# MCU.net
KiCad netlist of a schematic drawn in Altium Designer
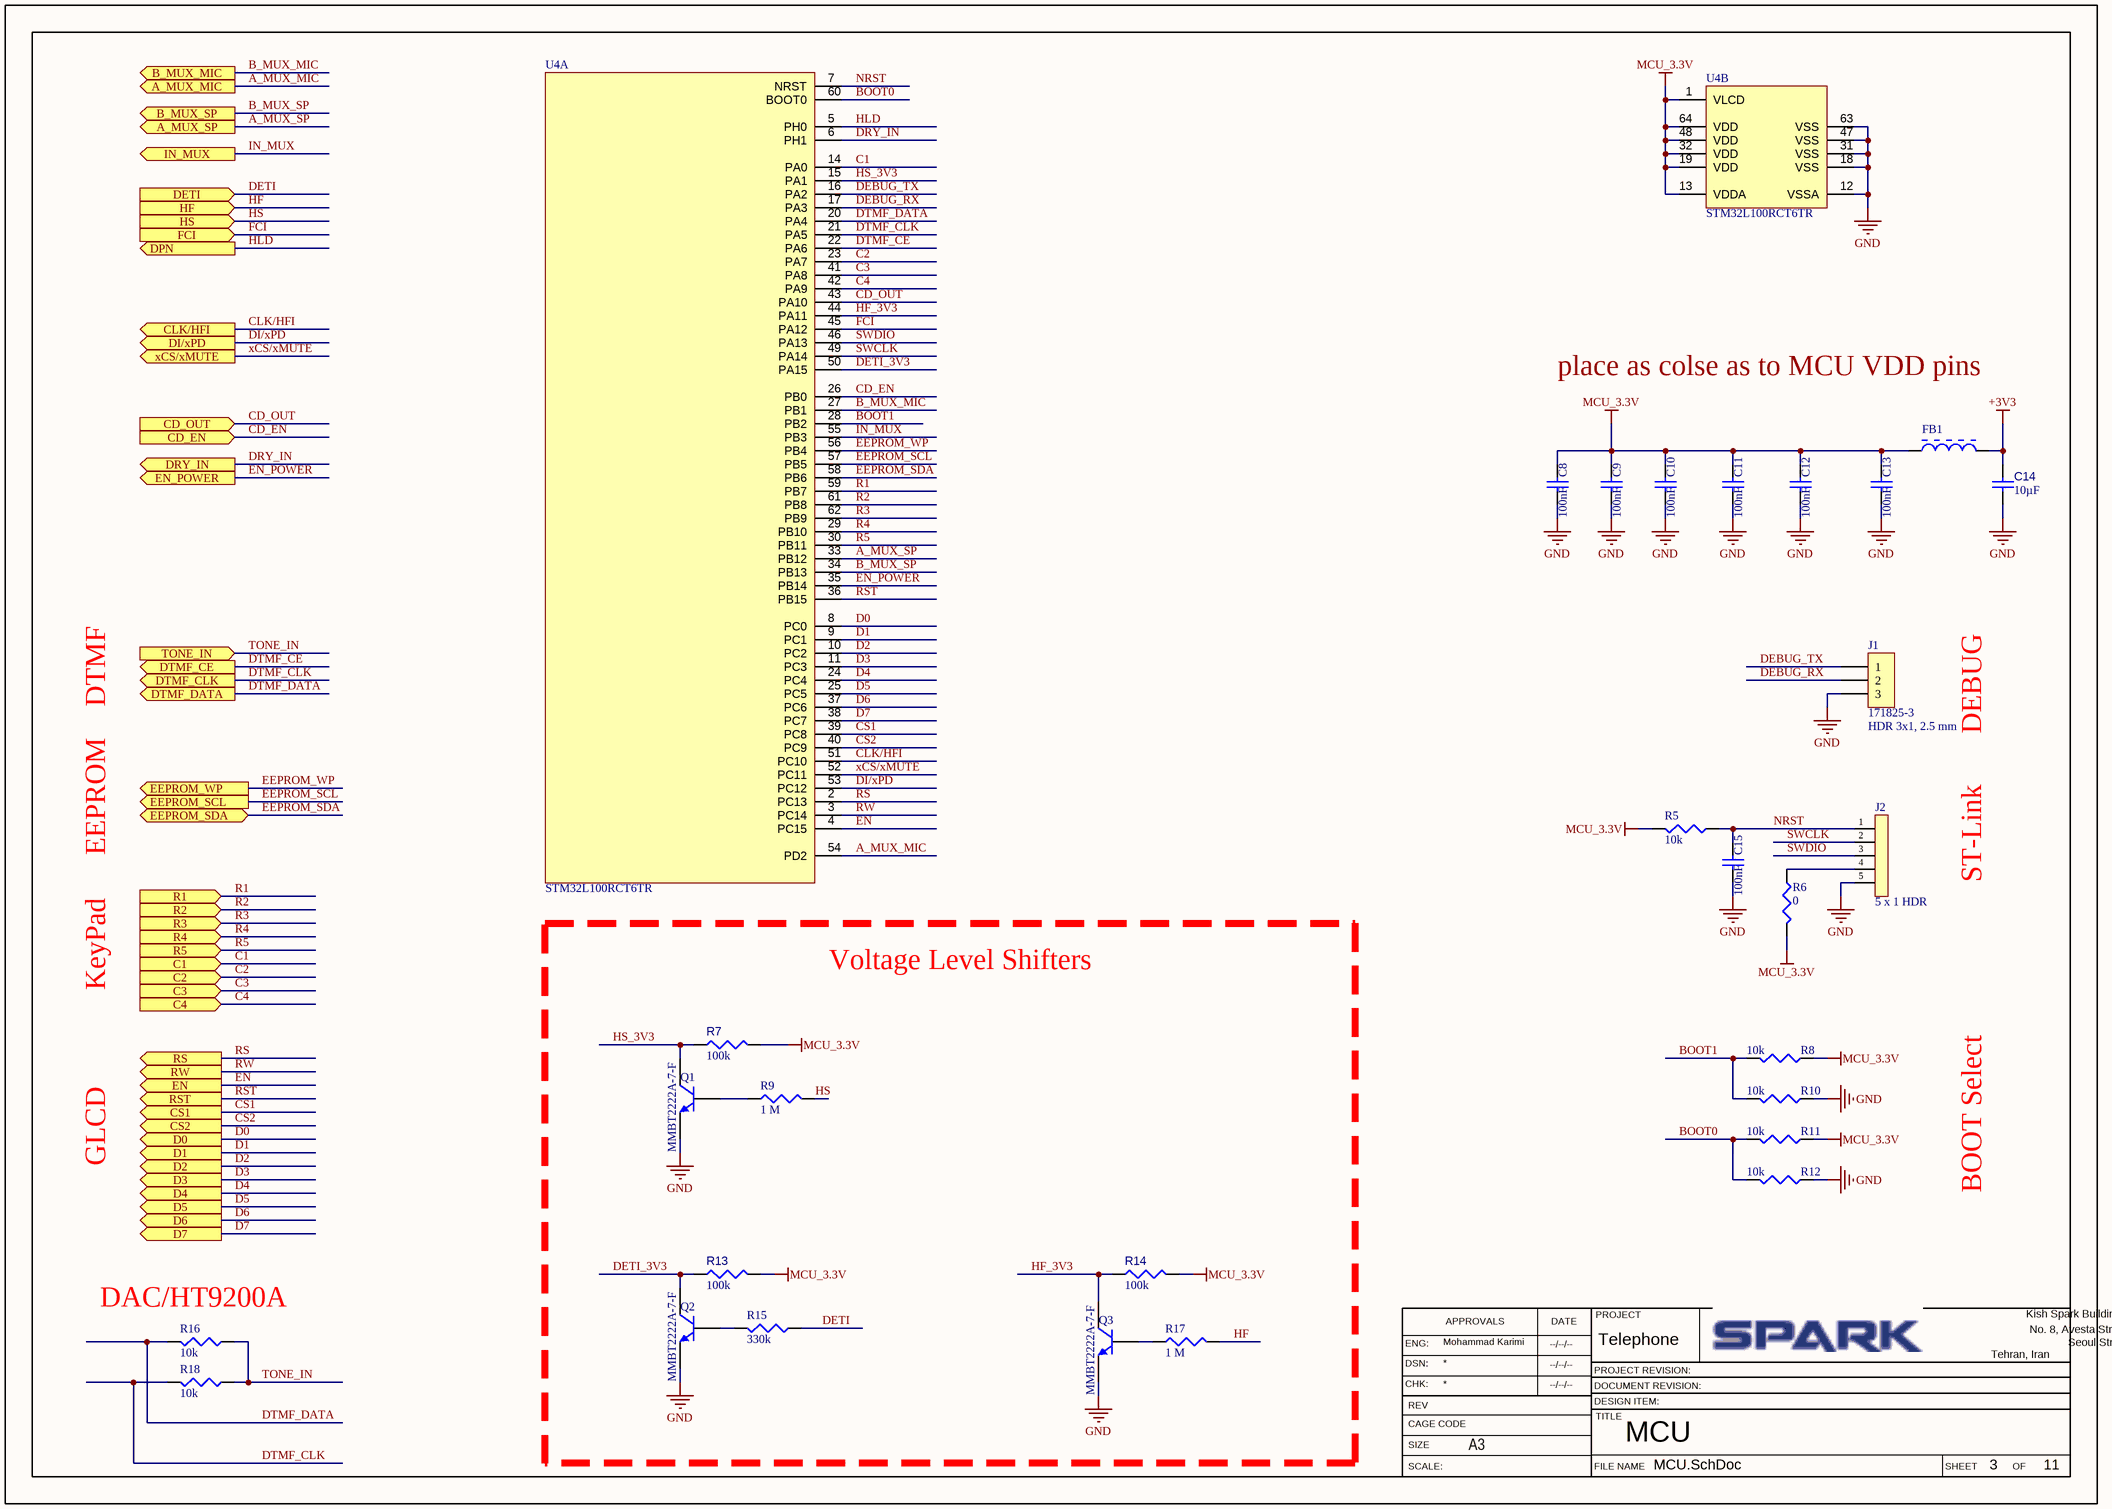
[diagram p0: MCU.SchDoc]

(export (version "E")
  (design (tool "Eeschema 10.0.6"))
  (components
    (comp (ref "C8")
      (value "100nF")
      (footprint "C0603")
      (description "YAGEO - CC0603KRX7R8BB104 - CERAMIC CAPACITOR, 0.1UF, 25V, X7R, 10%, 0603, FULL REEL")
      (fields
        (field (name "TOLERANCE") "10%")
        (field (name "VOLTAGE") "25V")
        (field (name "SOURCE") "PTZLib.SchLib")
      )
      (libsource (lib "Kish Spark") (part "CAP-NP-2"))
    )
    (comp (ref "C9")
      (value "100nF")
      (footprint "C0603")
      (description "YAGEO - CC0603KRX7R8BB104 - CERAMIC CAPACITOR, 0.1UF, 25V, X7R, 10%, 0603, FULL REEL")
      (fields
        (field (name "TOLERANCE") "10%")
        (field (name "VOLTAGE") "25V")
        (field (name "SOURCE") "PTZLib.SchLib")
      )
      (libsource (lib "Kish Spark") (part "CAP-NP-2"))
    )
    (comp (ref "C10")
      (value "100nF")
      (footprint "C0603")
      (description "YAGEO - CC0603KRX7R8BB104 - CERAMIC CAPACITOR, 0.1UF, 25V, X7R, 10%, 0603, FULL REEL")
      (fields
        (field (name "TOLERANCE") "10%")
        (field (name "VOLTAGE") "25V")
        (field (name "SOURCE") "PTZLib.SchLib")
      )
      (libsource (lib "Kish Spark") (part "CAP-NP-2"))
    )
    (comp (ref "C11")
      (value "100nF")
      (footprint "C0603")
      (description "YAGEO - CC0603KRX7R8BB104 - CERAMIC CAPACITOR, 0.1UF, 25V, X7R, 10%, 0603, FULL REEL")
      (fields
        (field (name "TOLERANCE") "10%")
        (field (name "VOLTAGE") "25V")
        (field (name "SOURCE") "PTZLib.SchLib")
      )
      (libsource (lib "Kish Spark") (part "CAP-NP-2"))
    )
    (comp (ref "C12")
      (value "100nF")
      (footprint "C0603")
      (description "YAGEO - CC0603KRX7R8BB104 - CERAMIC CAPACITOR, 0.1UF, 25V, X7R, 10%, 0603, FULL REEL")
      (fields
        (field (name "TOLERANCE") "10%")
        (field (name "VOLTAGE") "25V")
        (field (name "SOURCE") "PTZLib.SchLib")
      )
      (libsource (lib "Kish Spark") (part "CAP-NP-2"))
    )
    (comp (ref "C13")
      (value "100nF")
      (footprint "C0603")
      (description "YAGEO - CC0603KRX7R8BB104 - CERAMIC CAPACITOR, 0.1UF, 25V, X7R, 10%, 0603, FULL REEL")
      (fields
        (field (name "TOLERANCE") "10%")
        (field (name "VOLTAGE") "25V")
        (field (name "SOURCE") "PTZLib.SchLib")
      )
      (libsource (lib "Kish Spark") (part "CAP-NP-2"))
    )
    (comp (ref "C14")
      (value "10µF")
      (footprint "0805")
      (description "Ceramic Capacitor, 10UF, 6.3V, X5R, 10%, 0805, Full Reel")
      (fields
        (field (name "MANUFACTURER") "KEMET")
        (field (name "MANUFACTURER PART NUMBER") "C0805C106K9PACTU")
      )
      (libsource (lib "Kish Spark") (part "CAP-NP-2"))
    )
    (comp (ref "C15")
      (value "100nF")
      (footprint "C0603")
      (description "YAGEO - CC0603KRX7R8BB104 - CERAMIC CAPACITOR, 0.1UF, 25V, X7R, 10%, 0603, FULL REEL")
      (fields
        (field (name "TOLERANCE") "10%")
        (field (name "VOLTAGE") "25V")
        (field (name "SOURCE") "PTZLib.SchLib")
      )
      (libsource (lib "Kish Spark") (part "CAP-NP-2"))
    )
    (comp (ref "FB1")
      (value "CMP-006-00051-1")
      (footprint "R0603")
      (description "Ferrite Beads 0603 60ohm")
      (fields (field (name "TOLERANCE") "25%") (field (name "SOURCE") "PTZLib.SchLib"))
      (libsource (lib "Kish Spark") (part "FerriteBead"))
    )
    (comp (ref "J1")
      (value "171825-3")
      (footprint "HDR_MALE_1x3_2.5MM_AMP EI_VERT")
      (description "EI Series 3 Position 2.5 mm Single Row Through Hole Shrouded Header")
      (fields (field (name "ALTIUM_VALUE") "HDR 3x1, 2.5 mm") (field (name "MANUFACTURER") "TE Connectivity"))
      (libsource (lib "Kish Spark") (part "171825-3"))
    )
    (comp (ref "J2")
      (value "5 x 1 HDR")
      (footprint "HDR_male_1x5_2.54mm")
      (description "Manufacturer Part # :   9-146278-0")
      (fields (field (name "SOURCE") "PTZLib.SchLib"))
      (libsource (lib "Kish Spark") (part "5 x 1 HDR"))
    )
    (comp (ref "Q1")
      (value "MMBT2222A-7-F")
      (footprint "SOT23127P600-8N")
      (description "MMBT2222 Series NPN 350 mW 40 V 600 mA SMT Small Signal Transistor - SOT-23")
      (fields
        (field (name "MANUFACTURER") "Diodes")
        (field (name "VOLTAGE") "40V")
        (field (name "SOURCE") "PTZ.SCHLIB")
      )
      (libsource (lib "Kish Spark") (part "BJT-NPN-EBC-3"))
    )
    (comp (ref "Q2")
      (value "MMBT2222A-7-F")
      (footprint "SOT23127P600-8N")
      (description "MMBT2222 Series NPN 350 mW 40 V 600 mA SMT Small Signal Transistor - SOT-23")
      (fields
        (field (name "MANUFACTURER") "Diodes")
        (field (name "VOLTAGE") "40V")
        (field (name "SOURCE") "PTZ.SCHLIB")
      )
      (libsource (lib "Kish Spark") (part "BJT-NPN-EBC-3"))
    )
    (comp (ref "Q3")
      (value "MMBT2222A-7-F")
      (footprint "SOT23127P600-8N")
      (description "MMBT2222 Series NPN 350 mW 40 V 600 mA SMT Small Signal Transistor - SOT-23")
      (fields
        (field (name "MANUFACTURER") "Diodes")
        (field (name "VOLTAGE") "40V")
        (field (name "SOURCE") "PTZ.SCHLIB")
      )
      (libsource (lib "Kish Spark") (part "BJT-NPN-EBC-3"))
    )
    (comp (ref "R5")
      (value "10k")
      (footprint "R0603")
      (description "Res Thick Film 0603 10K Ohm 5% 1/10W 200ppm/C Molded SMD SMD Paper T/R")
      (fields
        (field (name "TOLERANCE") "5%")
        (field (name "Comment") "CRCW060310K0JNEA")
        (field (name "SOURCE") "PTZLib.SchLib")
      )
      (libsource (lib "Kish Spark") (part "RN73R1JTTD3302F10"))
    )
    (comp (ref "R6")
      (value "0")
      (footprint "0805")
      (description "RC Series 0805 0.125 W 0 Ohm Jumper SMT Thick Film Chip Resistor")
      (fields
        (field (name "MANUFACTURER") "Yageo")
        (field (name "MANUFACTURER PART NUMBER") "RC0805FR-070RL")
      )
      (libsource (lib "Kish Spark") (part "RC0805FR-1018KL (2)"))
    )
    (comp (ref "R7")
      (value "100k")
      (footprint "R0805")
      (description "Res Thick Film 0805 100K Ohm 1% 1/8W ±100ppm/°C Molded SMD Paper T/R")
      (fields (field (name "POWER") "125mW") (field (name "TOLERANCE") "1%"))
      (libsource (lib "Kish Spark") (part "RES-2"))
    )
    (comp (ref "R8")
      (value "10k")
      (footprint "R0603")
      (description "Res Thick Film 0603 10K Ohm 5% 1/10W 200ppm/C Molded SMD SMD Paper T/R")
      (fields
        (field (name "TOLERANCE") "5%")
        (field (name "Comment") "CRCW060310K0JNEA")
        (field (name "SOURCE") "PTZLib.SchLib")
      )
      (libsource (lib "Kish Spark") (part "RN73R1JTTD3302F10"))
    )
    (comp (ref "R9")
      (value "1 M")
      (footprint "0805")
      (description "Res Thick Film 0805 1M Ohm 5% 0.125W(1/8W) ±200ppm/°C Pad SMD T/R")
      (fields
        (field (name "MANUFACTURER") "Vishay")
        (field (name "MANUFACTURER PART NUMBER") "CRCW08051M00JNEAC")
      )
      (libsource (lib "Kish Spark") (part "RC0805FR-1018KL (2)"))
    )
    (comp (ref "R10")
      (value "10k")
      (footprint "R0603")
      (description "Res Thick Film 0603 10K Ohm 5% 1/10W 200ppm/C Molded SMD SMD Paper T/R")
      (fields
        (field (name "TOLERANCE") "5%")
        (field (name "Comment") "CRCW060310K0JNEA")
        (field (name "SOURCE") "PTZLib.SchLib")
      )
      (libsource (lib "Kish Spark") (part "RN73R1JTTD3302F10"))
    )
    (comp (ref "R11")
      (value "10k")
      (footprint "R0603")
      (description "Res Thick Film 0603 10K Ohm 5% 1/10W 200ppm/C Molded SMD SMD Paper T/R")
      (fields
        (field (name "TOLERANCE") "5%")
        (field (name "Comment") "CRCW060310K0JNEA")
        (field (name "SOURCE") "PTZLib.SchLib")
      )
      (libsource (lib "Kish Spark") (part "RN73R1JTTD3302F10"))
    )
    (comp (ref "R12")
      (value "10k")
      (footprint "R0603")
      (description "Res Thick Film 0603 10K Ohm 5% 1/10W 200ppm/C Molded SMD SMD Paper T/R")
      (fields
        (field (name "TOLERANCE") "5%")
        (field (name "Comment") "CRCW060310K0JNEA")
        (field (name "SOURCE") "PTZLib.SchLib")
      )
      (libsource (lib "Kish Spark") (part "RN73R1JTTD3302F10"))
    )
    (comp (ref "R13")
      (value "100k")
      (footprint "R0805")
      (description "Res Thick Film 0805 100K Ohm 1% 1/8W ±100ppm/°C Molded SMD Paper T/R")
      (fields (field (name "POWER") "125mW") (field (name "TOLERANCE") "1%"))
      (libsource (lib "Kish Spark") (part "RES-2"))
    )
    (comp (ref "R14")
      (value "100k")
      (footprint "R0805")
      (description "Res Thick Film 0805 100K Ohm 1% 1/8W ±100ppm/°C Molded SMD Paper T/R")
      (fields (field (name "POWER") "125mW") (field (name "TOLERANCE") "1%"))
      (libsource (lib "Kish Spark") (part "RES-2"))
    )
    (comp (ref "R15")
      (value "330k")
      (footprint "0805")
      (description "Res Thick Film 0805 330K Ohm 1% 1/8W ±100ppm/°C Molded SMD Paper T/R")
      (fields
        (field (name "MANUFACTURER") "Yageo")
        (field (name "MANUFACTURER PART NUMBER") "RC0805FR-07330KL")
      )
      (libsource (lib "Kish Spark") (part "RC0805FR-1018KL (2)"))
    )
    (comp (ref "R16")
      (value "10k")
      (footprint "R0603")
      (description "Res Thick Film 0603 10K Ohm 5% 1/10W 200ppm/C Molded SMD SMD Paper T/R")
      (fields
        (field (name "TOLERANCE") "5%")
        (field (name "Comment") "CRCW060310K0JNEA")
        (field (name "SOURCE") "PTZLib.SchLib")
      )
      (libsource (lib "Kish Spark") (part "RN73R1JTTD3302F10"))
    )
    (comp (ref "R17")
      (value "1 M")
      (footprint "0805")
      (description "Res Thick Film 0805 1M Ohm 5% 0.125W(1/8W) ±200ppm/°C Pad SMD T/R")
      (fields
        (field (name "MANUFACTURER") "Vishay")
        (field (name "MANUFACTURER PART NUMBER") "CRCW08051M00JNEAC")
      )
      (libsource (lib "Kish Spark") (part "RC0805FR-1018KL (2)"))
    )
    (comp (ref "R18")
      (value "10k")
      (footprint "R0603")
      (description "Res Thick Film 0603 10K Ohm 5% 1/10W 200ppm/C Molded SMD SMD Paper T/R")
      (fields
        (field (name "TOLERANCE") "5%")
        (field (name "Comment") "CRCW060310K0JNEA")
        (field (name "SOURCE") "PTZLib.SchLib")
      )
      (libsource (lib "Kish Spark") (part "RN73R1JTTD3302F10"))
    )
    (comp (ref "U4")
      (value "STM32L100RCT6TR")
      (footprint "STM32L100RCT6TR-Footprint-1")
      (description "Ultra-low-power 32-bit Value Line ARM Cortex-M3 MCU with 256 Kbytes Flash, 32 MHz CPU, LCD, USB")
      (fields (field (name "MANUFACTURER") "STMicroelectronics"))
      (libsource (lib "Kish Spark") (part "STM32L100RCT6TR"))
    )
  )
  (nets
    (net (code "1") (name "+3V3") (class "Default")
      (node (ref "C14") (pin "1") (pinfunction "1_1") (pintype "passive"))
      (node (ref "FB1") (pin "2") (pinfunction "2_2") (pintype "passive"))
    )
    (net (code "2") (name "/A_MUX_MIC") (class "Default")
      (node (ref "U4") (pin "54") (pinfunction "PD2_54") (pintype "passive"))
    )
    (net (code "3") (name "/A_MUX_SP") (class "Default")
      (node (ref "U4") (pin "33") (pinfunction "PB12_33") (pintype "passive"))
    )
    (net (code "4") (name "/BOOT0") (class "Default")
      (node (ref "R11") (pin "2") (pinfunction "2_2") (pintype "passive"))
      (node (ref "R12") (pin "2") (pinfunction "2_2") (pintype "passive"))
      (node (ref "U4") (pin "60") (pinfunction "BOOT0_60") (pintype "passive"))
    )
    (net (code "5") (name "/BOOT1") (class "Default")
      (node (ref "R10") (pin "2") (pinfunction "2_2") (pintype "passive"))
      (node (ref "R8") (pin "2") (pinfunction "2_2") (pintype "passive"))
      (node (ref "U4") (pin "28") (pinfunction "PB2_28") (pintype "passive"))
    )
    (net (code "6") (name "/B_MUX_MIC") (class "Default")
      (node (ref "U4") (pin "27") (pinfunction "PB1_27") (pintype "passive"))
    )
    (net (code "7") (name "/B_MUX_SP") (class "Default")
      (node (ref "U4") (pin "34") (pinfunction "PB13_34") (pintype "passive"))
    )
    (net (code "8") (name "/C1") (class "Default")
      (node (ref "U4") (pin "14") (pinfunction "PA0_14") (pintype "passive"))
    )
    (net (code "9") (name "/C2") (class "Default")
      (node (ref "U4") (pin "23") (pinfunction "PA7_23") (pintype "passive"))
    )
    (net (code "10") (name "/C3") (class "Default")
      (node (ref "U4") (pin "41") (pinfunction "PA8_41") (pintype "passive"))
    )
    (net (code "11") (name "/C4") (class "Default")
      (node (ref "U4") (pin "42") (pinfunction "PA9_42") (pintype "passive"))
    )
    (net (code "12") (name "/CD_EN") (class "Default")
      (node (ref "U4") (pin "26") (pinfunction "PB0_26") (pintype "passive"))
    )
    (net (code "13") (name "/CD_OUT") (class "Default")
      (node (ref "U4") (pin "43") (pinfunction "PA10_43") (pintype "passive"))
    )
    (net (code "14") (name "/CLK{slash}HFI") (class "Default")
      (node (ref "U4") (pin "51") (pinfunction "PC10_51") (pintype "passive"))
    )
    (net (code "15") (name "/CS1") (class "Default")
      (node (ref "U4") (pin "39") (pinfunction "PC8_39") (pintype "passive"))
    )
    (net (code "16") (name "/CS2") (class "Default")
      (node (ref "U4") (pin "40") (pinfunction "PC9_40") (pintype "passive"))
    )
    (net (code "17") (name "/D0") (class "Default")
      (node (ref "U4") (pin "8") (pinfunction "PC0_8") (pintype "passive"))
    )
    (net (code "18") (name "/D1") (class "Default")
      (node (ref "U4") (pin "9") (pinfunction "PC1_9") (pintype "passive"))
    )
    (net (code "19") (name "/D2") (class "Default")
      (node (ref "U4") (pin "10") (pinfunction "PC2_10") (pintype "passive"))
    )
    (net (code "20") (name "/D3") (class "Default")
      (node (ref "U4") (pin "11") (pinfunction "PC3_11") (pintype "passive"))
    )
    (net (code "21") (name "/D4") (class "Default")
      (node (ref "U4") (pin "24") (pinfunction "PC4_24") (pintype "passive"))
    )
    (net (code "22") (name "/D5") (class "Default")
      (node (ref "U4") (pin "25") (pinfunction "PC5_25") (pintype "passive"))
    )
    (net (code "23") (name "/D6") (class "Default")
      (node (ref "U4") (pin "37") (pinfunction "PC6_37") (pintype "passive"))
    )
    (net (code "24") (name "/D7") (class "Default")
      (node (ref "U4") (pin "38") (pinfunction "PC7_38") (pintype "passive"))
    )
    (net (code "25") (name "/DEBUG_RX") (class "Default")
      (node (ref "J1") (pin "2") (pinfunction "2_2") (pintype "passive"))
      (node (ref "U4") (pin "17") (pinfunction "PA3_17") (pintype "passive"))
    )
    (net (code "26") (name "/DEBUG_TX") (class "Default")
      (node (ref "J1") (pin "1") (pinfunction "1_1") (pintype "passive"))
      (node (ref "U4") (pin "16") (pinfunction "PA2_16") (pintype "passive"))
    )
    (net (code "27") (name "/DETI") (class "Default")
      (node (ref "R15") (pin "1") (pinfunction "1_1") (pintype "passive"))
    )
    (net (code "28") (name "/DETI_3V3") (class "Default")
      (node (ref "Q2") (pin "3") (pinfunction "C_3") (pintype "passive"))
      (node (ref "R13") (pin "1") (pinfunction "1_1") (pintype "passive"))
      (node (ref "U4") (pin "50") (pinfunction "PA15_50") (pintype "passive"))
    )
    (net (code "29") (name "/DI{slash}xPD") (class "Default")
      (node (ref "U4") (pin "53") (pinfunction "PC12_53") (pintype "passive"))
    )
    (net (code "30") (name "/DRY_IN") (class "Default")
      (node (ref "U4") (pin "6") (pinfunction "PH1_6") (pintype "passive"))
    )
    (net (code "31") (name "/DTMF_CE") (class "Default")
      (node (ref "U4") (pin "22") (pinfunction "PA6_22") (pintype "passive"))
    )
    (net (code "32") (name "/DTMF_CLK") (class "Default")
      (node (ref "R18") (pin "2") (pinfunction "2_2") (pintype "passive"))
      (node (ref "U4") (pin "21") (pinfunction "PA5_21") (pintype "passive"))
    )
    (net (code "33") (name "/DTMF_DATA") (class "Default")
      (node (ref "R16") (pin "2") (pinfunction "2_2") (pintype "passive"))
      (node (ref "U4") (pin "20") (pinfunction "PA4_20") (pintype "passive"))
    )
    (net (code "34") (name "/EEPROM_SCL") (class "Default")
      (node (ref "U4") (pin "57") (pinfunction "PB5_57") (pintype "passive"))
    )
    (net (code "35") (name "/EEPROM_SDA") (class "Default")
      (node (ref "U4") (pin "58") (pinfunction "PB6_58") (pintype "passive"))
    )
    (net (code "36") (name "/EEPROM_WP") (class "Default")
      (node (ref "U4") (pin "56") (pinfunction "PB4_56") (pintype "passive"))
    )
    (net (code "37") (name "/EN") (class "Default")
      (node (ref "U4") (pin "4") (pinfunction "PC15_4") (pintype "passive"))
    )
    (net (code "38") (name "/EN_POWER") (class "Default")
      (node (ref "U4") (pin "35") (pinfunction "PB14_35") (pintype "passive"))
    )
    (net (code "39") (name "/FCI") (class "Default")
      (node (ref "U4") (pin "45") (pinfunction "PA12_45") (pintype "passive"))
    )
    (net (code "40") (name "/HF") (class "Default")
      (node (ref "R17") (pin "2") (pinfunction "2_2") (pintype "passive"))
    )
    (net (code "41") (name "/HF_3V3") (class "Default")
      (node (ref "Q3") (pin "3") (pinfunction "C_3") (pintype "passive"))
      (node (ref "R14") (pin "1") (pinfunction "1_1") (pintype "passive"))
      (node (ref "U4") (pin "44") (pinfunction "PA11_44") (pintype "passive"))
    )
    (net (code "42") (name "/HLD") (class "Default")
      (node (ref "U4") (pin "5") (pinfunction "PH0_5") (pintype "passive"))
    )
    (net (code "43") (name "/HS") (class "Default")
      (node (ref "R9") (pin "2") (pinfunction "2_2") (pintype "passive"))
    )
    (net (code "44") (name "/HS_3V3") (class "Default")
      (node (ref "Q1") (pin "3") (pinfunction "C_3") (pintype "passive"))
      (node (ref "R7") (pin "1") (pinfunction "1_1") (pintype "passive"))
      (node (ref "U4") (pin "15") (pinfunction "PA1_15") (pintype "passive"))
    )
    (net (code "45") (name "/IN_MUX") (class "Default")
      (node (ref "U4") (pin "55") (pinfunction "PB3_55") (pintype "passive"))
    )
    (net (code "46") (name "/NRST") (class "Default")
      (node (ref "C15") (pin "1") (pinfunction "1_1") (pintype "passive"))
      (node (ref "J2") (pin "1") (pinfunction "1_1") (pintype "passive"))
      (node (ref "R5") (pin "1") (pinfunction "1_1") (pintype "passive"))
      (node (ref "U4") (pin "7") (pinfunction "NRST_7") (pintype "passive"))
    )
    (net (code "47") (name "/R1") (class "Default")
      (node (ref "U4") (pin "59") (pinfunction "PB7_59") (pintype "passive"))
    )
    (net (code "48") (name "/R2") (class "Default")
      (node (ref "U4") (pin "61") (pinfunction "PB8_61") (pintype "passive"))
    )
    (net (code "49") (name "/R3") (class "Default")
      (node (ref "U4") (pin "62") (pinfunction "PB9_62") (pintype "passive"))
    )
    (net (code "50") (name "/R4") (class "Default")
      (node (ref "U4") (pin "29") (pinfunction "PB10_29") (pintype "passive"))
    )
    (net (code "51") (name "/R5") (class "Default")
      (node (ref "U4") (pin "30") (pinfunction "PB11_30") (pintype "passive"))
    )
    (net (code "52") (name "/RS") (class "Default")
      (node (ref "U4") (pin "2") (pinfunction "PC13_2") (pintype "passive"))
    )
    (net (code "53") (name "/RST") (class "Default")
      (node (ref "U4") (pin "36") (pinfunction "PB15_36") (pintype "passive"))
    )
    (net (code "54") (name "/RW") (class "Default")
      (node (ref "U4") (pin "3") (pinfunction "PC14_3") (pintype "passive"))
    )
    (net (code "55") (name "/SWCLK") (class "Default")
      (node (ref "J2") (pin "2") (pinfunction "2_2") (pintype "passive"))
      (node (ref "U4") (pin "49") (pinfunction "PA14_49") (pintype "passive"))
    )
    (net (code "56") (name "/SWDIO") (class "Default")
      (node (ref "J2") (pin "3") (pinfunction "3_3") (pintype "passive"))
      (node (ref "U4") (pin "46") (pinfunction "PA13_46") (pintype "passive"))
    )
    (net (code "57") (name "/TONE_IN") (class "Default")
      (node (ref "R16") (pin "1") (pinfunction "1_1") (pintype "passive"))
      (node (ref "R18") (pin "1") (pinfunction "1_1") (pintype "passive"))
    )
    (net (code "58") (name "/xCS{slash}xMUTE") (class "Default")
      (node (ref "U4") (pin "52") (pinfunction "PC11_52") (pintype "passive"))
    )
    (net (code "59") (name "GND") (class "Default")
      (node (ref "C10") (pin "2") (pinfunction "2_2") (pintype "passive"))
      (node (ref "C11") (pin "2") (pinfunction "2_2") (pintype "passive"))
      (node (ref "C12") (pin "2") (pinfunction "2_2") (pintype "passive"))
      (node (ref "C13") (pin "2") (pinfunction "2_2") (pintype "passive"))
      (node (ref "C14") (pin "2") (pinfunction "2_2") (pintype "passive"))
      (node (ref "C15") (pin "2") (pinfunction "2_2") (pintype "passive"))
      (node (ref "C8") (pin "2") (pinfunction "2_2") (pintype "passive"))
      (node (ref "C9") (pin "2") (pinfunction "2_2") (pintype "passive"))
      (node (ref "J1") (pin "3") (pinfunction "3_3") (pintype "passive"))
      (node (ref "J2") (pin "5") (pinfunction "5_5") (pintype "passive"))
      (node (ref "Q1") (pin "1") (pinfunction "E_1") (pintype "passive"))
      (node (ref "Q2") (pin "1") (pinfunction "E_1") (pintype "passive"))
      (node (ref "Q3") (pin "1") (pinfunction "E_1") (pintype "passive"))
      (node (ref "R10") (pin "1") (pinfunction "1_1") (pintype "passive"))
      (node (ref "R12") (pin "1") (pinfunction "1_1") (pintype "passive"))
      (node (ref "U4") (pin "12") (pinfunction "VSSA_12") (pintype "power_in"))
      (node (ref "U4") (pin "18") (pinfunction "VSS_18") (pintype "power_in"))
      (node (ref "U4") (pin "31") (pinfunction "VSS_31") (pintype "power_in"))
      (node (ref "U4") (pin "47") (pinfunction "VSS_47") (pintype "power_in"))
      (node (ref "U4") (pin "63") (pinfunction "VSS_63") (pintype "power_in"))
    )
    (net (code "60") (name "MCU_3.3V") (class "Default")
      (node (ref "C10") (pin "1") (pinfunction "1_1") (pintype "passive"))
      (node (ref "C11") (pin "1") (pinfunction "1_1") (pintype "passive"))
      (node (ref "C12") (pin "1") (pinfunction "1_1") (pintype "passive"))
      (node (ref "C13") (pin "1") (pinfunction "1_1") (pintype "passive"))
      (node (ref "C8") (pin "1") (pinfunction "1_1") (pintype "passive"))
      (node (ref "C9") (pin "1") (pinfunction "1_1") (pintype "passive"))
      (node (ref "FB1") (pin "1") (pinfunction "1_1") (pintype "passive"))
      (node (ref "R11") (pin "1") (pinfunction "1_1") (pintype "passive"))
      (node (ref "R13") (pin "2") (pinfunction "2_2") (pintype "passive"))
      (node (ref "R14") (pin "2") (pinfunction "2_2") (pintype "passive"))
      (node (ref "R5") (pin "2") (pinfunction "2_2") (pintype "passive"))
      (node (ref "R6") (pin "2") (pinfunction "2_2") (pintype "passive"))
      (node (ref "R7") (pin "2") (pinfunction "2_2") (pintype "passive"))
      (node (ref "R8") (pin "1") (pinfunction "1_1") (pintype "passive"))
      (node (ref "U4") (pin "1") (pinfunction "VLCD_1") (pintype "power_in"))
      (node (ref "U4") (pin "13") (pinfunction "VDDA_13") (pintype "power_in"))
      (node (ref "U4") (pin "19") (pinfunction "VDD_19") (pintype "power_in"))
      (node (ref "U4") (pin "32") (pinfunction "VDD_32") (pintype "power_in"))
      (node (ref "U4") (pin "48") (pinfunction "VDD_48") (pintype "power_in"))
      (node (ref "U4") (pin "64") (pinfunction "VDD_64") (pintype "power_in"))
    )
    (net (code "61") (name "Net-(J2-Pad4)") (class "Default")
      (node (ref "J2") (pin "4") (pinfunction "4_4") (pintype "passive"))
      (node (ref "R6") (pin "1") (pinfunction "1_1") (pintype "passive"))
    )
    (net (code "62") (name "Net-(Q1-B)") (class "Default")
      (node (ref "Q1") (pin "2") (pinfunction "B_2") (pintype "passive"))
      (node (ref "R9") (pin "1") (pinfunction "1_1") (pintype "passive"))
    )
    (net (code "63") (name "Net-(Q2-B)") (class "Default")
      (node (ref "Q2") (pin "2") (pinfunction "B_2") (pintype "passive"))
      (node (ref "R15") (pin "2") (pinfunction "2_2") (pintype "passive"))
    )
    (net (code "64") (name "Net-(Q3-B)") (class "Default")
      (node (ref "Q3") (pin "2") (pinfunction "B_2") (pintype "passive"))
      (node (ref "R17") (pin "1") (pinfunction "1_1") (pintype "passive"))
    )
  )
)
